# MCU.net
KiCad netlist of a schematic drawn in Altium Designer
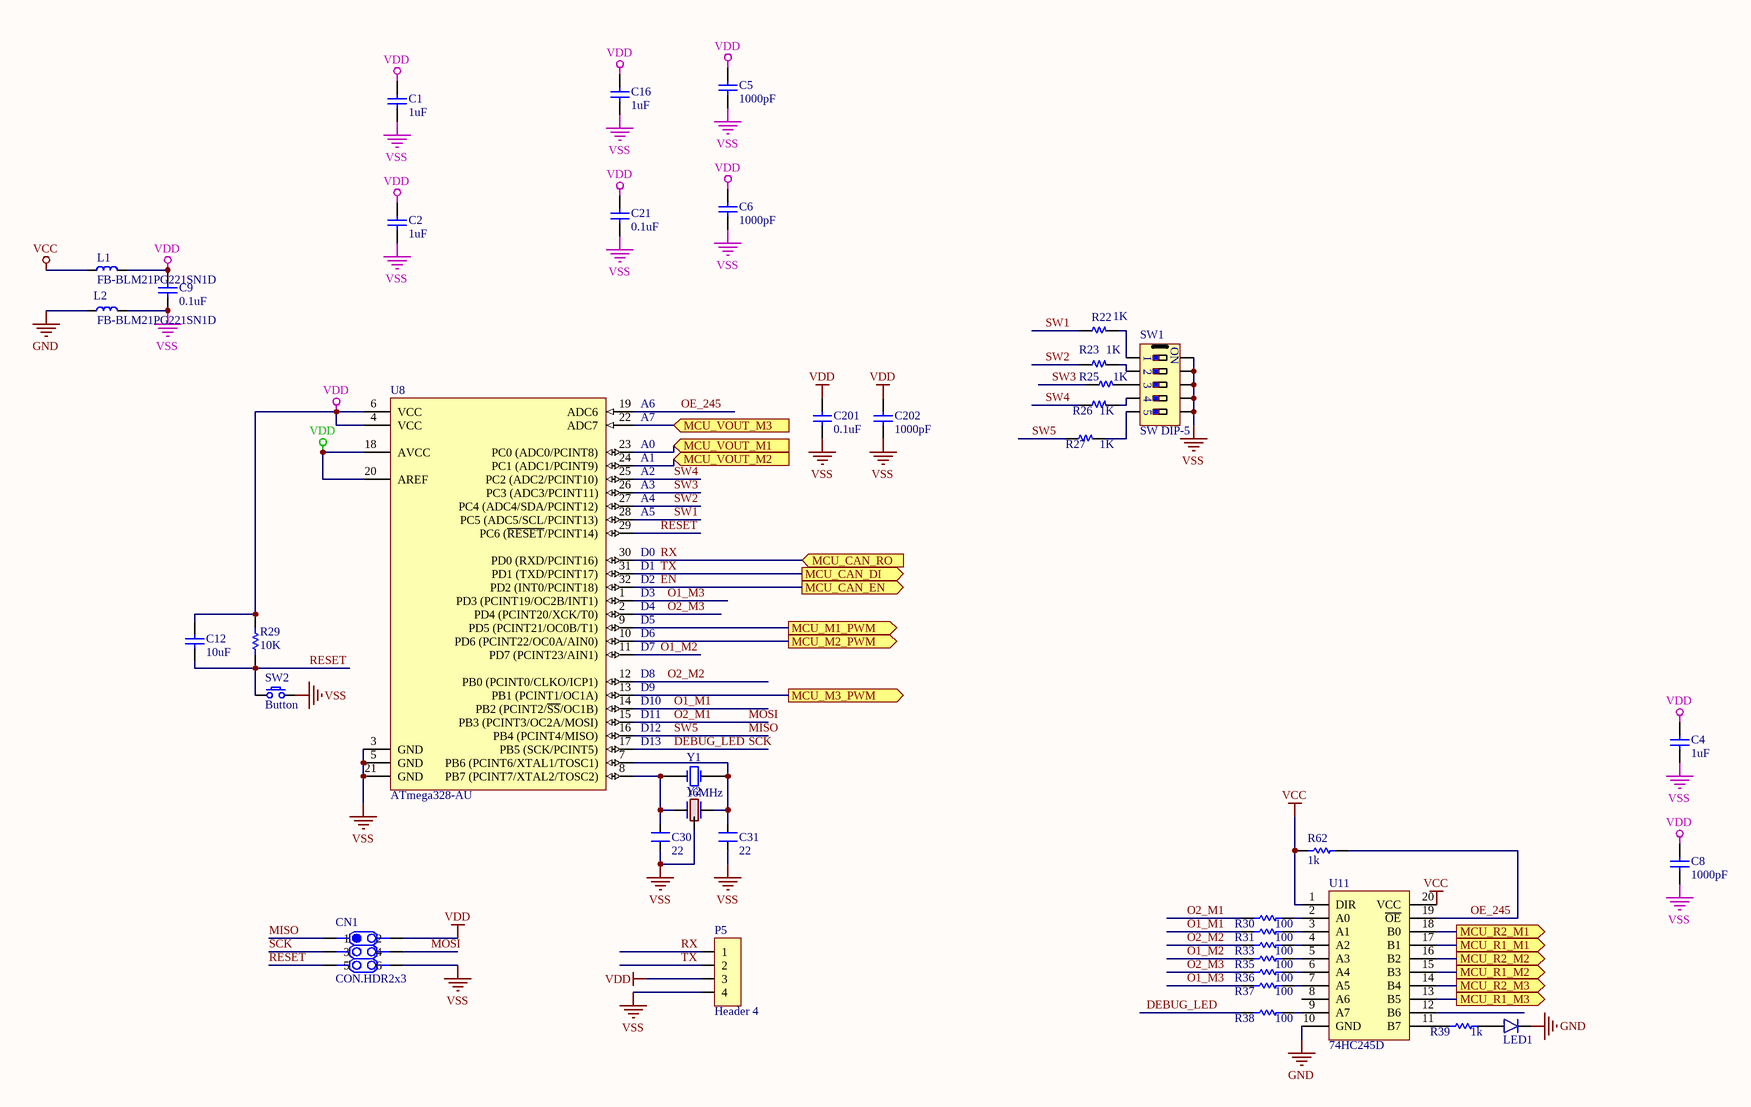
[diagram p0: MCU.SchDoc]

(export (version "E")
  (design (tool "Eeschema 10.0.6"))
  (components
    (comp (ref "C1")
      (value "1uF")
      (footprint "C 0805 (2012)")
      (description "Capacitor non-pol")
      (libsource (lib "BKIT4U_LIB") (part "Capacitor NP"))
    )
    (comp (ref "C2")
      (value "1uF")
      (footprint "C 0805 (2012)")
      (description "Capacitor non-pol")
      (libsource (lib "BKIT4U_LIB") (part "Capacitor NP"))
    )
    (comp (ref "C4")
      (value "1uF")
      (footprint "C 0805 (2012)")
      (description "Capacitor non-pol")
      (libsource (lib "BKIT4U_LIB") (part "Capacitor NP"))
    )
    (comp (ref "C5")
      (value "1000pF")
      (footprint "C 0805 (2012)")
      (description "Capacitor non-pol")
      (libsource (lib "BKIT4U_LIB") (part "Capacitor NP"))
    )
    (comp (ref "C6")
      (value "1000pF")
      (footprint "C 0805 (2012)")
      (description "Capacitor non-pol")
      (libsource (lib "BKIT4U_LIB") (part "Capacitor NP"))
    )
    (comp (ref "C8")
      (value "1000pF")
      (footprint "C 0805 (2012)")
      (description "Capacitor non-pol")
      (libsource (lib "BKIT4U_LIB") (part "Capacitor NP"))
    )
    (comp (ref "C9")
      (value "0.1uF")
      (footprint "C 0805")
      (description "CAP CER 0.1UF 50V X7R 0603")
      (libsource (lib "chipfc_altium_libs") (part "Capacitor NP"))
    )
    (comp (ref "C12")
      (value "10uF")
      (footprint "C 0805")
      (description "Capacitor non-pol")
      (libsource (lib "BKIT4U_LIB") (part "Capacitor NP"))
    )
    (comp (ref "C16")
      (value "1uF")
      (footprint "C 0805 (2012)")
      (description "Capacitor non-pol")
      (libsource (lib "BKIT4U_LIB") (part "Capacitor NP"))
    )
    (comp (ref "C21")
      (value "0.1uF")
      (footprint "C 0805 (2012)")
      (description "Capacitor non-pol")
      (libsource (lib "BKIT4U_LIB") (part "Capacitor NP"))
    )
    (comp (ref "C30")
      (value "22")
      (footprint "C 0805")
      (description "Cap np 104 => 105pF")
      (libsource (lib "syhaunguyen") (part "CN2"))
    )
    (comp (ref "C31")
      (value "22")
      (footprint "C 0805")
      (description "Cap np 104 => 105pF")
      (libsource (lib "syhaunguyen") (part "CN2"))
    )
    (comp (ref "C201")
      (value "0.1uF")
      (footprint "C 0805")
      (description "Capacitor non-pol")
      (libsource (lib "BKIT4U_LIB") (part "Capacitor NP"))
    )
    (comp (ref "C202")
      (value "1000pF")
      (footprint "C 0805")
      (description "Capacitor non-pol")
      (libsource (lib "BKIT4U_LIB") (part "Capacitor NP"))
    )
    (comp (ref "CN1")
      (value "CON.HDR2x3")
      (footprint "Header 3x2")
      (description "Header 2x3")
      (fields (field (name "PUBLISHER") "Hoang Nguyen"))
      (libsource (lib "phong") (part "CON.HDR2x3"))
    )
    (comp (ref "L1")
      (value "FB-BLM21PG221SN1D")
      (footprint "L 0805 (2012)")
      (description "Inductor")
      (libsource (lib "chipfc_altium_libs") (part "Inductor"))
    )
    (comp (ref "L2")
      (value "FB-BLM21PG221SN1D")
      (footprint "L 0805 (2012)")
      (description "Inductor")
      (libsource (lib "chipfc_altium_libs") (part "Inductor"))
    )
    (comp (ref "LED1")
      (value "Led")
      (footprint "Led SMD 0805")
      (description "Typical LED")
      (libsource (lib "BKIT4U_LIB") (part "Led"))
    )
    (comp (ref "P5")
      (value "Header 4")
      (footprint "Header 4")
      (description "Header, 4-Pin")
      (libsource (lib "BKIT4U_LIB") (part "Header 4"))
    )
    (comp (ref "R22")
      (value "1K")
      (footprint "R 0805")
      (description "Resistor")
      (libsource (lib "chipfc_altium_libs") (part "Resistor"))
    )
    (comp (ref "R23")
      (value "1K")
      (footprint "R 0805")
      (description "Resistor")
      (libsource (lib "chipfc_altium_libs") (part "Resistor"))
    )
    (comp (ref "R25")
      (value "1K")
      (footprint "R 0805")
      (description "Resistor")
      (libsource (lib "chipfc_altium_libs") (part "Resistor"))
    )
    (comp (ref "R26")
      (value "1K")
      (footprint "R 0805")
      (description "Resistor")
      (libsource (lib "chipfc_altium_libs") (part "Resistor"))
    )
    (comp (ref "R27")
      (value "1K")
      (footprint "R 0805")
      (description "Resistor")
      (libsource (lib "chipfc_altium_libs") (part "Resistor"))
    )
    (comp (ref "R29")
      (value "10K")
      (footprint "R 0805")
      (description "Resistor")
      (fields (field (name "PUBLISHER") "Altium Limited"))
      (libsource (lib "phong") (part "Resistor"))
    )
    (comp (ref "R30")
      (value "100")
      (footprint "R 0805")
      (description "Resistor")
      (fields (field (name "PUBLISHER") "Altium Limited"))
      (libsource (lib "BKIT4U_LIB") (part "Resistor"))
    )
    (comp (ref "R31")
      (value "100")
      (footprint "R 0805")
      (description "Resistor")
      (fields (field (name "PUBLISHER") "Altium Limited"))
      (libsource (lib "BKIT4U_LIB") (part "Resistor"))
    )
    (comp (ref "R33")
      (value "100")
      (footprint "R 0805")
      (description "Resistor")
      (fields (field (name "PUBLISHER") "Altium Limited"))
      (libsource (lib "BKIT4U_LIB") (part "Resistor"))
    )
    (comp (ref "R35")
      (value "100")
      (footprint "R 0805")
      (description "Resistor")
      (fields (field (name "PUBLISHER") "Altium Limited"))
      (libsource (lib "BKIT4U_LIB") (part "Resistor"))
    )
    (comp (ref "R36")
      (value "100")
      (footprint "R 0805")
      (description "Resistor")
      (fields (field (name "PUBLISHER") "Altium Limited"))
      (libsource (lib "BKIT4U_LIB") (part "Resistor"))
    )
    (comp (ref "R37")
      (value "100")
      (footprint "R 0805")
      (description "Resistor")
      (fields (field (name "PUBLISHER") "Altium Limited"))
      (libsource (lib "BKIT4U_LIB") (part "Resistor"))
    )
    (comp (ref "R38")
      (value "100")
      (footprint "R 0805")
      (description "Resistor")
      (fields (field (name "PUBLISHER") "Altium Limited"))
      (libsource (lib "BKIT4U_LIB") (part "Resistor"))
    )
    (comp (ref "R39")
      (value "1k")
      (footprint "R 0805")
      (description "Resistor")
      (fields (field (name "PUBLISHER") "Altium Limited"))
      (libsource (lib "BKIT4U_LIB") (part "Resistor"))
    )
    (comp (ref "R62")
      (value "1k")
      (footprint "R 0805")
      (description "Resistor")
      (fields (field (name "PUBLISHER") "Altium Limited"))
      (libsource (lib "BKIT4U_LIB") (part "Resistor"))
    )
    (comp (ref "SW1")
      (value "SW DIP-5")
      (footprint "SW/DIP5/300")
      (libsource (lib "chipfc_altium_libs") (part "SW DIP-5"))
    )
    (comp (ref "SW2")
      (value "Button")
      (footprint "SW/2/SMD")
      (description "Tact switch 2 pin")
      (libsource (lib "BKIT4U_LIB") (part "SW SPST"))
    )
    (comp (ref "U8")
      (value "ATmega328-AU")
      (footprint "QFP32N")
      (fields (field (name "PUBLISHER") "Altium Limited"))
      (libsource (lib "Atmel Microcontroller 8-Bit megaAVR") (part "ATmega328-AU"))
    )
    (comp (ref "U11")
      (value "74HC245D")
      (footprint "SOIC-20")
      (description "IC TRANSCVR NON-INVERT 6V 20SO")
      (libsource (lib "chipfc_altium_libs") (part "74HC245D"))
    )
    (comp (ref "Y1")
      (value "16MHz")
      (footprint "XTAL")
      (description "Crystal Oscillator")
      (fields (field (name "PUBLISHER") "Altium Limited"))
      (libsource (lib "phong") (part "XTAL"))
    )
    (comp (ref "Y2")
      (value "~")
      (footprint "Crystal SMD CSTCE")
      (libsource (lib "BKIT4U_LIB") (part "Crystal CSTCE"))
    )
  )
  (nets
    (net (code "1") (name "/DEBUG_LED") (class "Default")
      (node (ref "CN1") (pin "3") (pinfunction "3_3") (pintype "passive"))
      (node (ref "R38") (pin "1") (pinfunction "1_1") (pintype "passive"))
      (node (ref "U8") (pin "17") (pinfunction "PB5_(SCK/PCINT5)_17") (pintype "bidirectional"))
    )
    (net (code "2") (name "/EN") (class "Default")
      (node (ref "U8") (pin "32") (pinfunction "PD2_(INT0/PCINT18)_32") (pintype "bidirectional"))
    )
    (net (code "3") (name "/MCU_M1_PWM") (class "Default")
      (node (ref "U8") (pin "9") (pinfunction "PD5_(PCINT21/OC0B/T1)_9") (pintype "bidirectional"))
    )
    (net (code "4") (name "/MCU_M2_PWM") (class "Default")
      (node (ref "U8") (pin "10") (pinfunction "PD6_(PCINT22/OC0A/AIN0)_10") (pintype "bidirectional"))
    )
    (net (code "5") (name "/MCU_M3_PWM") (class "Default")
      (node (ref "U8") (pin "13") (pinfunction "PB1_(PCINT1/OC1A)_13") (pintype "bidirectional"))
    )
    (net (code "6") (name "/MCU_R1_M1") (class "Default")
      (node (ref "U11") (pin "17") (pinfunction "B1_17") (pintype "passive"))
    )
    (net (code "7") (name "/MCU_R1_M2") (class "Default")
      (node (ref "U11") (pin "15") (pinfunction "B3_15") (pintype "passive"))
    )
    (net (code "8") (name "/MCU_R1_M3") (class "Default")
      (node (ref "U11") (pin "13") (pinfunction "B5_13") (pintype "passive"))
    )
    (net (code "9") (name "/MCU_R2_M1") (class "Default")
      (node (ref "U11") (pin "18") (pinfunction "B0_18") (pintype "passive"))
    )
    (net (code "10") (name "/MCU_R2_M2") (class "Default")
      (node (ref "U11") (pin "16") (pinfunction "B2_16") (pintype "passive"))
    )
    (net (code "11") (name "/MCU_R2_M3") (class "Default")
      (node (ref "U11") (pin "14") (pinfunction "B4_14") (pintype "passive"))
    )
    (net (code "12") (name "/MCU_VOUT_M1") (class "Default")
      (node (ref "U8") (pin "23") (pinfunction "PC0_(ADC0/PCINT8)_23") (pintype "bidirectional"))
    )
    (net (code "13") (name "/MCU_VOUT_M2") (class "Default")
      (node (ref "U8") (pin "24") (pinfunction "PC1_(ADC1/PCINT9)_24") (pintype "bidirectional"))
    )
    (net (code "14") (name "/MCU_VOUT_M3") (class "Default")
      (node (ref "U8") (pin "22") (pinfunction "ADC7_22") (pintype "input"))
    )
    (net (code "15") (name "/MISO") (class "Default")
      (node (ref "CN1") (pin "1") (pinfunction "1_1") (pintype "passive"))
      (node (ref "R27") (pin "1") (pinfunction "1_1") (pintype "passive"))
      (node (ref "U8") (pin "16") (pinfunction "PB4_(PCINT4/MISO)_16") (pintype "bidirectional"))
    )
    (net (code "16") (name "/MOSI") (class "Default")
      (node (ref "CN1") (pin "4") (pinfunction "4_4") (pintype "passive"))
      (node (ref "R30") (pin "1") (pinfunction "1_1") (pintype "passive"))
      (node (ref "U8") (pin "15") (pinfunction "PB3_(PCINT3/OC2A/MOSI)_15") (pintype "bidirectional"))
    )
    (net (code "17") (name "/O1_M1") (class "Default")
      (node (ref "R31") (pin "1") (pinfunction "1_1") (pintype "passive"))
      (node (ref "U8") (pin "14") (pinfunction "PB2_(PCINT2/~{SS}/OC1B)_14") (pintype "bidirectional"))
    )
    (net (code "18") (name "/O1_M2") (class "Default")
      (node (ref "R35") (pin "1") (pinfunction "1_1") (pintype "passive"))
      (node (ref "U8") (pin "11") (pinfunction "PD7_(PCINT23/AIN1)_11") (pintype "bidirectional"))
    )
    (net (code "19") (name "/O1_M3") (class "Default")
      (node (ref "R37") (pin "1") (pinfunction "1_1") (pintype "passive"))
      (node (ref "U8") (pin "1") (pinfunction "PD3_(PCINT19/OC2B/INT1)_1") (pintype "bidirectional"))
    )
    (net (code "20") (name "/O2_M2") (class "Default")
      (node (ref "R33") (pin "1") (pinfunction "1_1") (pintype "passive"))
      (node (ref "U8") (pin "12") (pinfunction "PB0_(PCINT0/CLKO/ICP1)_12") (pintype "bidirectional"))
    )
    (net (code "21") (name "/O2_M3") (class "Default")
      (node (ref "R36") (pin "1") (pinfunction "1_1") (pintype "passive"))
      (node (ref "U8") (pin "2") (pinfunction "PD4_(PCINT20/XCK/T0)_2") (pintype "bidirectional"))
    )
    (net (code "22") (name "/OE_245") (class "Default")
      (node (ref "R62") (pin "2") (pinfunction "2_2") (pintype "passive"))
      (node (ref "U11") (pin "19") (pinfunction "~{OE}_19") (pintype "passive"))
      (node (ref "U8") (pin "19") (pinfunction "ADC6_19") (pintype "input"))
    )
    (net (code "23") (name "/RESET") (class "Default")
      (node (ref "C12") (pin "2") (pinfunction "2_2") (pintype "passive"))
      (node (ref "CN1") (pin "5") (pinfunction "5_5") (pintype "passive"))
      (node (ref "R29") (pin "1") (pinfunction "1_1") (pintype "passive"))
      (node (ref "SW2") (pin "1") (pinfunction "1_1") (pintype "passive"))
      (node (ref "U8") (pin "29") (pinfunction "PC6_(~{RESET}/PCINT14)_29") (pintype "bidirectional"))
    )
    (net (code "24") (name "/RX") (class "Default")
      (node (ref "P5") (pin "1") (pinfunction "1_1") (pintype "passive"))
      (node (ref "U8") (pin "30") (pinfunction "PD0_(RXD/PCINT16)_30") (pintype "bidirectional"))
    )
    (net (code "25") (name "/SW1") (class "Default")
      (node (ref "R22") (pin "1") (pinfunction "1_1") (pintype "passive"))
      (node (ref "U8") (pin "28") (pinfunction "PC5_(ADC5/SCL/PCINT13)_28") (pintype "bidirectional"))
    )
    (net (code "26") (name "/SW2") (class "Default")
      (node (ref "R23") (pin "1") (pinfunction "1_1") (pintype "passive"))
      (node (ref "U8") (pin "27") (pinfunction "PC4_(ADC4/SDA/PCINT12)_27") (pintype "bidirectional"))
    )
    (net (code "27") (name "/SW3") (class "Default")
      (node (ref "R25") (pin "1") (pinfunction "1_1") (pintype "passive"))
      (node (ref "U8") (pin "26") (pinfunction "PC3_(ADC3/PCINT11)_26") (pintype "bidirectional"))
    )
    (net (code "28") (name "/SW4") (class "Default")
      (node (ref "R26") (pin "1") (pinfunction "1_1") (pintype "passive"))
      (node (ref "U8") (pin "25") (pinfunction "PC2_(ADC2/PCINT10)_25") (pintype "bidirectional"))
    )
    (net (code "29") (name "/TX") (class "Default")
      (node (ref "P5") (pin "2") (pinfunction "2_2") (pintype "passive"))
      (node (ref "U8") (pin "31") (pinfunction "PD1_(TXD/PCINT17)_31") (pintype "bidirectional"))
    )
    (net (code "30") (name "GND") (class "Default")
      (node (ref "L2") (pin "1") (pinfunction "1_1") (pintype "passive"))
      (node (ref "LED1") (pin "2") (pinfunction "K_2") (pintype "passive"))
      (node (ref "U11") (pin "10") (pinfunction "GND_10") (pintype "passive"))
    )
    (net (code "31") (name "Net-(LED1-A)") (class "Default")
      (node (ref "LED1") (pin "1") (pinfunction "A_1") (pintype "passive"))
      (node (ref "R39") (pin "2") (pinfunction "2_2") (pintype "passive"))
    )
    (net (code "32") (name "Net-(R22-Pad2)") (class "Default")
      (node (ref "R22") (pin "2") (pinfunction "2_2") (pintype "passive"))
      (node (ref "SW1") (pin "1") (pinfunction "1_1") (pintype "passive"))
    )
    (net (code "33") (name "Net-(R23-Pad2)") (class "Default")
      (node (ref "R23") (pin "2") (pinfunction "2_2") (pintype "passive"))
      (node (ref "SW1") (pin "2") (pinfunction "2_2") (pintype "passive"))
    )
    (net (code "34") (name "Net-(R25-Pad2)") (class "Default")
      (node (ref "R25") (pin "2") (pinfunction "2_2") (pintype "passive"))
      (node (ref "SW1") (pin "3") (pinfunction "3_3") (pintype "passive"))
    )
    (net (code "35") (name "Net-(R26-Pad2)") (class "Default")
      (node (ref "R26") (pin "2") (pinfunction "2_2") (pintype "passive"))
      (node (ref "SW1") (pin "4") (pinfunction "4_4") (pintype "passive"))
    )
    (net (code "36") (name "Net-(R27-Pad2)") (class "Default")
      (node (ref "R27") (pin "2") (pinfunction "2_2") (pintype "passive"))
      (node (ref "SW1") (pin "5") (pinfunction "5_5") (pintype "passive"))
    )
    (net (code "37") (name "Net-(U8-PB6_(PCINT6{slash}XTAL1{slash}TOSC1))") (class "Default")
      (node (ref "C31") (pin "2") (pinfunction "2_2") (pintype "passive"))
      (node (ref "U8") (pin "7") (pinfunction "PB6_(PCINT6/XTAL1/TOSC1)_7") (pintype "bidirectional"))
      (node (ref "Y1") (pin "2") (pinfunction "OSC2_2") (pintype "passive"))
      (node (ref "Y2") (pin "1") (pinfunction "1_1") (pintype "passive"))
    )
    (net (code "38") (name "Net-(U8-PB7_(PCINT7{slash}XTAL2{slash}TOSC2))") (class "Default")
      (node (ref "C30") (pin "2") (pinfunction "2_2") (pintype "passive"))
      (node (ref "U8") (pin "8") (pinfunction "PB7_(PCINT7/XTAL2/TOSC2)_8") (pintype "bidirectional"))
      (node (ref "Y1") (pin "1") (pinfunction "OSC1_1") (pintype "passive"))
      (node (ref "Y2") (pin "3") (pinfunction "3_3") (pintype "passive"))
    )
    (net (code "39") (name "Net-(U11-A0)") (class "Default")
      (node (ref "R30") (pin "2") (pinfunction "2_2") (pintype "passive"))
      (node (ref "U11") (pin "2") (pinfunction "A0_2") (pintype "passive"))
    )
    (net (code "40") (name "Net-(U11-A1)") (class "Default")
      (node (ref "R31") (pin "2") (pinfunction "2_2") (pintype "passive"))
      (node (ref "U11") (pin "3") (pinfunction "A1_3") (pintype "passive"))
    )
    (net (code "41") (name "Net-(U11-A2)") (class "Default")
      (node (ref "R33") (pin "2") (pinfunction "2_2") (pintype "passive"))
      (node (ref "U11") (pin "4") (pinfunction "A2_4") (pintype "passive"))
    )
    (net (code "42") (name "Net-(U11-A3)") (class "Default")
      (node (ref "R35") (pin "2") (pinfunction "2_2") (pintype "passive"))
      (node (ref "U11") (pin "5") (pinfunction "A3_5") (pintype "passive"))
    )
    (net (code "43") (name "Net-(U11-A4)") (class "Default")
      (node (ref "R36") (pin "2") (pinfunction "2_2") (pintype "passive"))
      (node (ref "U11") (pin "6") (pinfunction "A4_6") (pintype "passive"))
    )
    (net (code "44") (name "Net-(U11-A5)") (class "Default")
      (node (ref "R37") (pin "2") (pinfunction "2_2") (pintype "passive"))
      (node (ref "U11") (pin "7") (pinfunction "A5_7") (pintype "passive"))
    )
    (net (code "45") (name "Net-(U11-A7)") (class "Default")
      (node (ref "R38") (pin "2") (pinfunction "2_2") (pintype "passive"))
      (node (ref "U11") (pin "9") (pinfunction "A7_9") (pintype "passive"))
    )
    (net (code "46") (name "Net-(U11-B7)") (class "Default")
      (node (ref "R39") (pin "1") (pinfunction "1_1") (pintype "passive"))
      (node (ref "U11") (pin "11") (pinfunction "B7_11") (pintype "passive"))
    )
    (net (code "47") (name "VCC") (class "Default")
      (node (ref "L1") (pin "1") (pinfunction "1_1") (pintype "passive"))
      (node (ref "R62") (pin "1") (pinfunction "1_1") (pintype "passive"))
      (node (ref "U11") (pin "1") (pinfunction "DIR_1") (pintype "passive"))
      (node (ref "U11") (pin "20") (pinfunction "VCC_20") (pintype "passive"))
    )
    (net (code "48") (name "VDD") (class "Default")
      (node (ref "C1") (pin "1") (pinfunction "1_1") (pintype "passive"))
      (node (ref "C12") (pin "1") (pinfunction "1_1") (pintype "passive"))
      (node (ref "C16") (pin "1") (pinfunction "1_1") (pintype "passive"))
      (node (ref "C2") (pin "1") (pinfunction "1_1") (pintype "passive"))
      (node (ref "C201") (pin "1") (pinfunction "1_1") (pintype "passive"))
      (node (ref "C202") (pin "1") (pinfunction "1_1") (pintype "passive"))
      (node (ref "C21") (pin "1") (pinfunction "1_1") (pintype "passive"))
      (node (ref "C4") (pin "1") (pinfunction "1_1") (pintype "passive"))
      (node (ref "C5") (pin "1") (pinfunction "1_1") (pintype "passive"))
      (node (ref "C6") (pin "1") (pinfunction "1_1") (pintype "passive"))
      (node (ref "C8") (pin "1") (pinfunction "1_1") (pintype "passive"))
      (node (ref "C9") (pin "1") (pinfunction "1_1") (pintype "passive"))
      (node (ref "CN1") (pin "2") (pinfunction "2_2") (pintype "passive"))
      (node (ref "L1") (pin "2") (pinfunction "2_2") (pintype "passive"))
      (node (ref "P5") (pin "3") (pinfunction "3_3") (pintype "passive"))
      (node (ref "R29") (pin "2") (pinfunction "2_2") (pintype "passive"))
      (node (ref "U8") (pin "18") (pinfunction "AVCC_18") (pintype "power_in"))
      (node (ref "U8") (pin "20") (pinfunction "AREF_20") (pintype "passive"))
      (node (ref "U8") (pin "4") (pinfunction "VCC_4") (pintype "power_in"))
      (node (ref "U8") (pin "6") (pinfunction "VCC_6") (pintype "power_in"))
    )
    (net (code "49") (name "VSS") (class "Default")
      (node (ref "C1") (pin "2") (pinfunction "2_2") (pintype "passive"))
      (node (ref "C16") (pin "2") (pinfunction "2_2") (pintype "passive"))
      (node (ref "C2") (pin "2") (pinfunction "2_2") (pintype "passive"))
      (node (ref "C201") (pin "2") (pinfunction "2_2") (pintype "passive"))
      (node (ref "C202") (pin "2") (pinfunction "2_2") (pintype "passive"))
      (node (ref "C21") (pin "2") (pinfunction "2_2") (pintype "passive"))
      (node (ref "C30") (pin "1") (pinfunction "1_1") (pintype "passive"))
      (node (ref "C31") (pin "1") (pinfunction "1_1") (pintype "passive"))
      (node (ref "C4") (pin "2") (pinfunction "2_2") (pintype "passive"))
      (node (ref "C5") (pin "2") (pinfunction "2_2") (pintype "passive"))
      (node (ref "C6") (pin "2") (pinfunction "2_2") (pintype "passive"))
      (node (ref "C8") (pin "2") (pinfunction "2_2") (pintype "passive"))
      (node (ref "C9") (pin "2") (pinfunction "2_2") (pintype "passive"))
      (node (ref "CN1") (pin "6") (pinfunction "6_6") (pintype "passive"))
      (node (ref "L2") (pin "2") (pinfunction "2_2") (pintype "passive"))
      (node (ref "P5") (pin "4") (pinfunction "4_4") (pintype "passive"))
      (node (ref "SW1") (pin "10") (pinfunction "10_10") (pintype "passive"))
      (node (ref "SW1") (pin "6") (pinfunction "6_6") (pintype "passive"))
      (node (ref "SW1") (pin "7") (pinfunction "7_7") (pintype "passive"))
      (node (ref "SW1") (pin "8") (pinfunction "8_8") (pintype "passive"))
      (node (ref "SW1") (pin "9") (pinfunction "9_9") (pintype "passive"))
      (node (ref "SW2") (pin "2") (pinfunction "2_2") (pintype "passive"))
      (node (ref "U8") (pin "21") (pinfunction "GND_21") (pintype "power_in"))
      (node (ref "U8") (pin "3") (pinfunction "GND_3") (pintype "power_in"))
      (node (ref "U8") (pin "5") (pinfunction "GND_5") (pintype "power_in"))
      (node (ref "Y2") (pin "2") (pinfunction "2_2") (pintype "passive"))
    )
    (net (code "50") (name "unconnected-(U11-A6-Pad8)") (class "Default")
      (node (ref "U11") (pin "8") (pinfunction "A6_8") (pintype "passive"))
    )
    (net (code "51") (name "unconnected-(U11-B6-Pad12)") (class "Default")
      (node (ref "U11") (pin "12") (pinfunction "B6_12") (pintype "passive"))
    )
  )
)
